# ProPrj_mfswControllerV1_2026-07-03.net
KiCad netlist of a schematic drawn in EasyEDA Pro
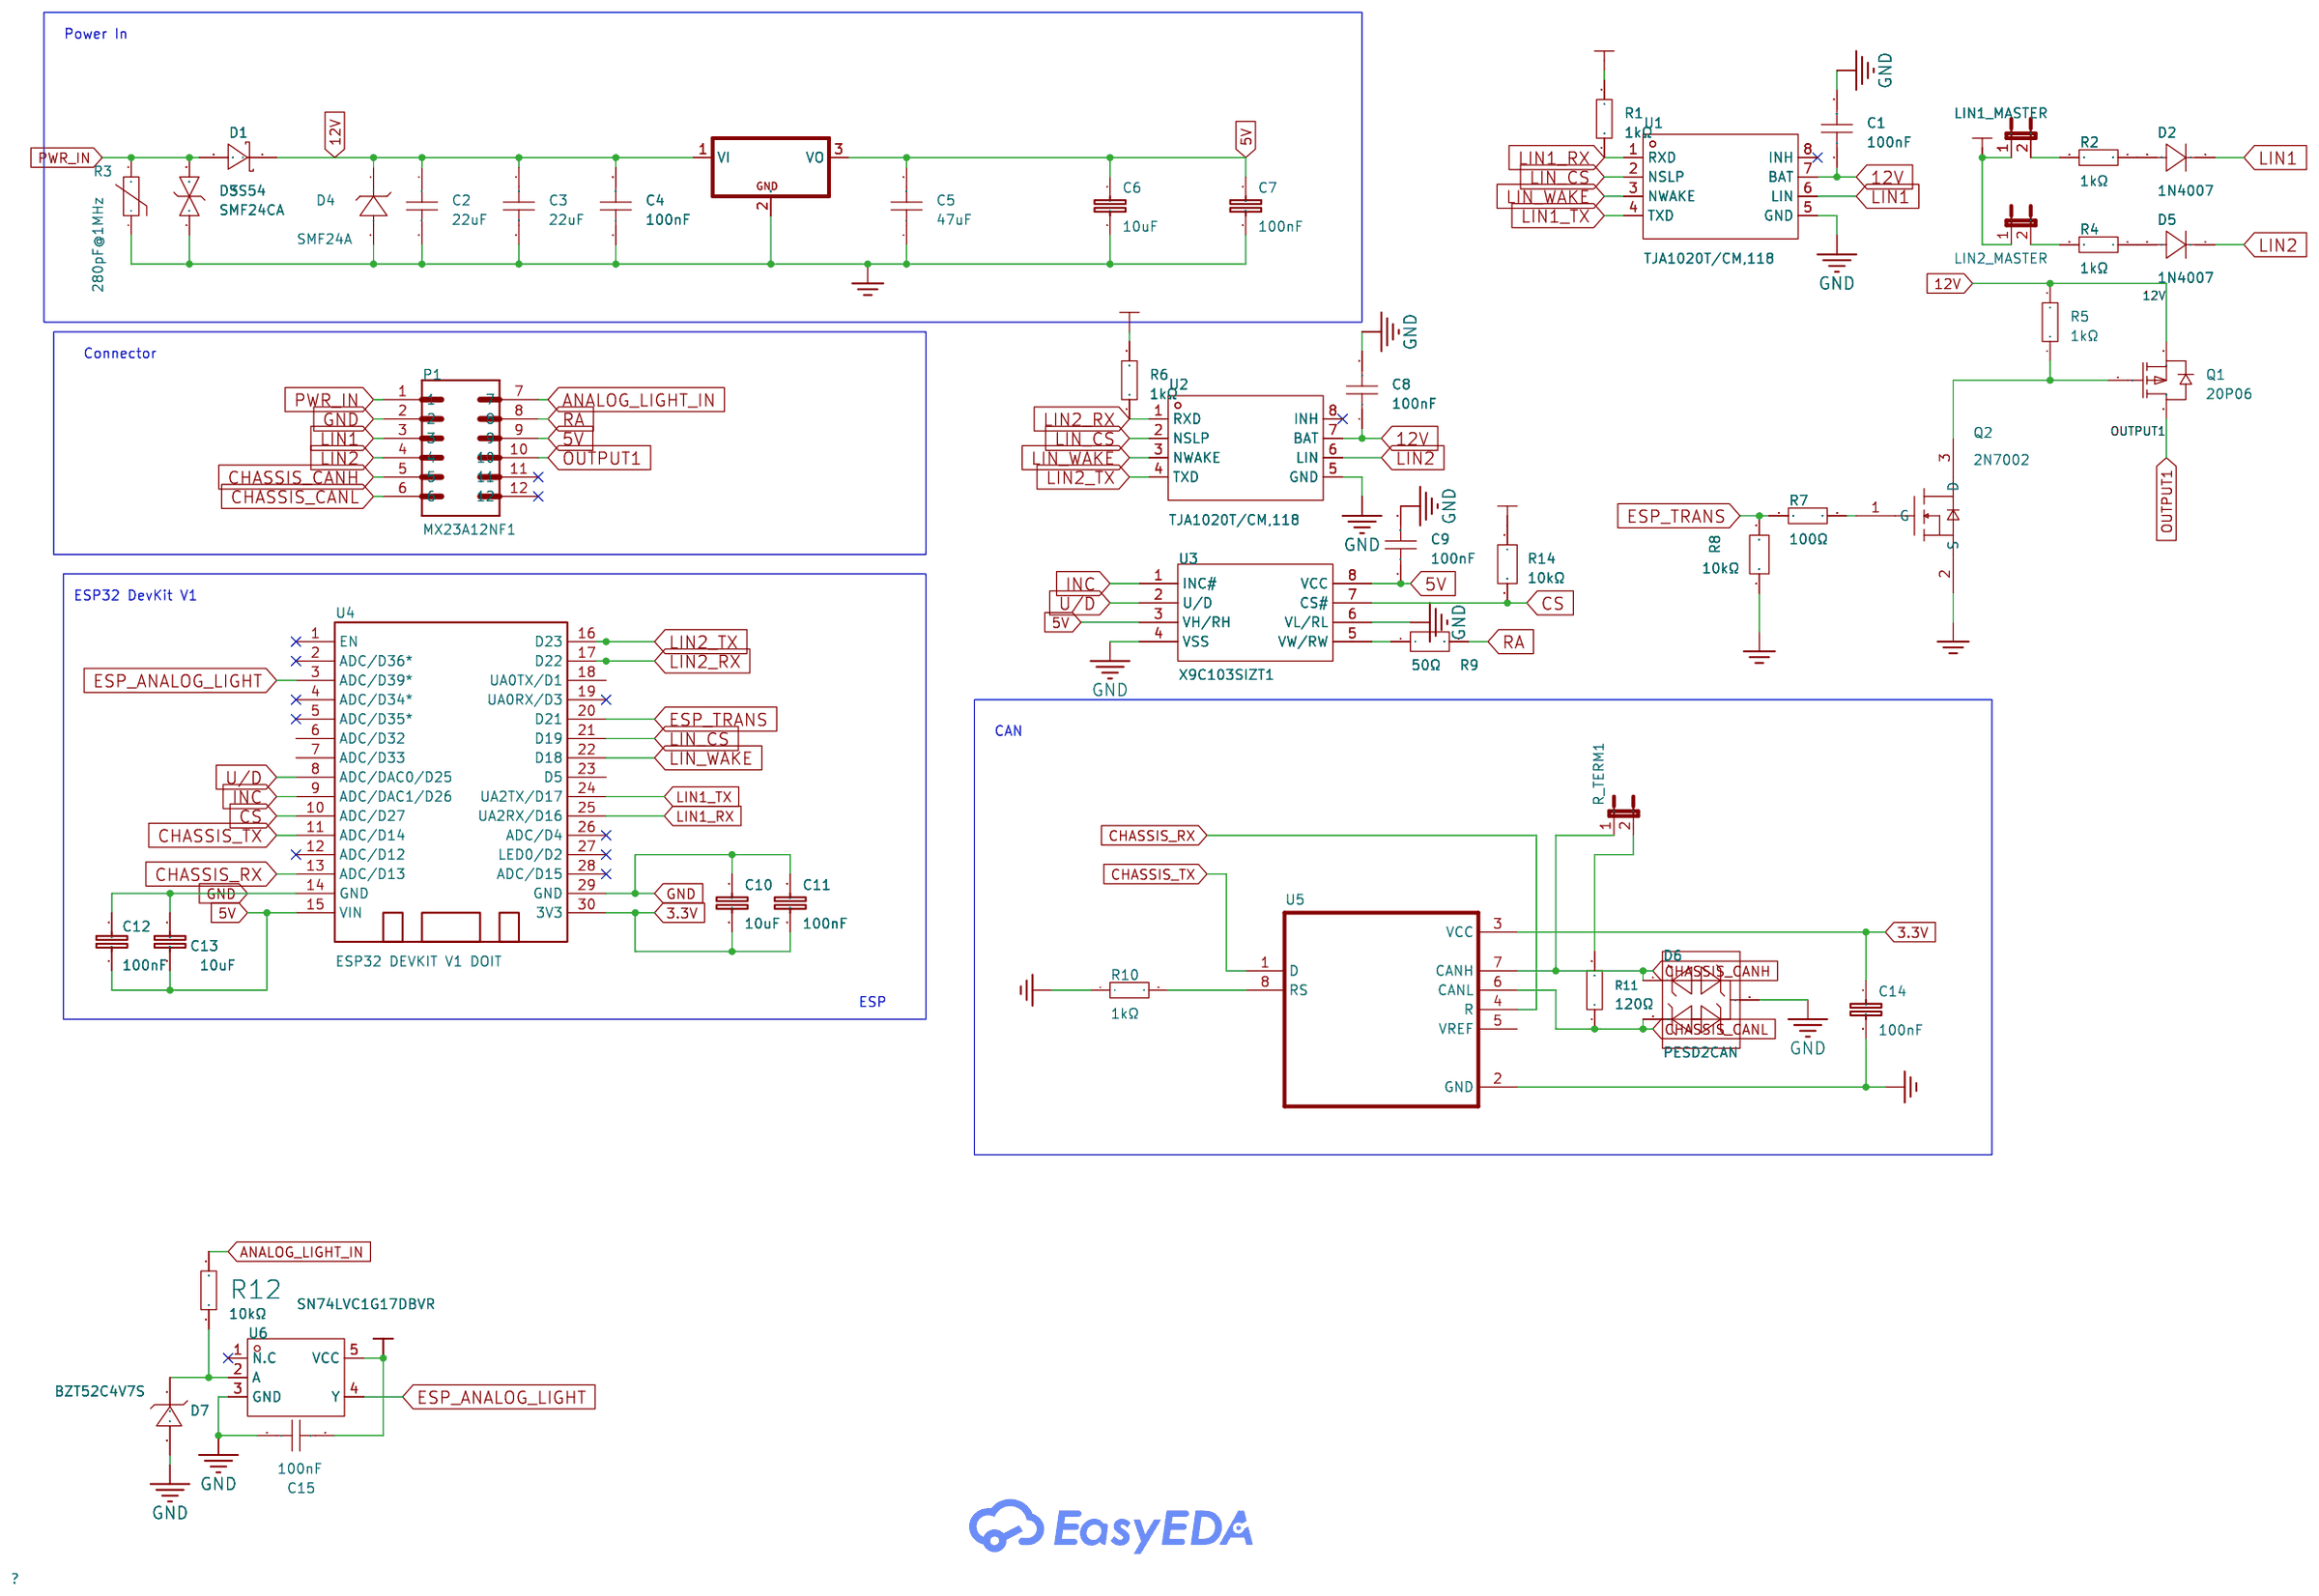
[diagram p0: schematic sheet]

(export (version "E")
  (design (tool "Eeschema 10.0.6"))
  (components
    (comp (ref "C1")
      (value "100nF")
      (footprint "easyedapro:C0603")
      (description "Capacitance:100nF Tolerance:±10% Tolerance:±10% Voltage Rating:50V Temperature Coefficient:X7R")
      (fields
        (field (name "Manufacturer Part") "CL10B104KB8NNNC")
        (field (name "Manufacturer") "SAMSUNG(三星)")
      )
      (libsource (lib "easyedapro") (part "CC0603KRX7R9BB104"))
    )
    (comp (ref "C2")
      (value "22uF")
      (footprint "easyedapro:C0805")
      (fields
        (field (name "Manufacturer Part") "HGC0805R5226M350NSLJ")
        (field (name "Manufacturer") "Chinocera(华瓷)")
      )
      (libsource (lib "easyedapro") (part "HGC0805R5226M350NSLJ"))
    )
    (comp (ref "C3")
      (value "22uF")
      (footprint "easyedapro:C0805")
      (fields
        (field (name "Manufacturer Part") "HGC0805R5226M350NSLJ")
        (field (name "Manufacturer") "Chinocera(华瓷)")
      )
      (libsource (lib "easyedapro") (part "HGC0805R5226M350NSLJ"))
    )
    (comp (ref "C4")
      (value "100nF")
      (description "Capacitance:100nF Tolerance:±10% Tolerance:±10% Voltage Rating:50V Temperature Coefficient:X7R")
      (fields
        (field (name "Manufacturer Part") "CL10B104KB8NNNC")
        (field (name "Manufacturer") "SAMSUNG(三星)")
      )
      (libsource (lib "easyedapro") (part "CSA0603X7R104K500JT"))
    )
    (comp (ref "C5")
      (value "47uF")
      (footprint "easyedapro:C0805")
      (description "Capacitance:47uF Tolerance:±20% Tolerance:±20% Voltage Rating:10V Temperature Coefficient:X5R")
      (fields
        (field (name "Manufacturer Part") "CL21A476MPYNNWE")
        (field (name "Manufacturer") "SAMSUNG(三星)")
      )
      (libsource (lib "easyedapro") (part "CL21A476MPYNNWE"))
    )
    (comp (ref "C6")
      (value "10uF")
      (fields
        (field (name "Manufacturer Part") "CL21A106KAYNNNE")
        (field (name "Manufacturer") "SAMSUNG(三星)")
      )
      (libsource (lib "easyedapro") (part "capacitor-wima_C_2.5/2"))
    )
    (comp (ref "C7")
      (value "100nF")
      (description "Capacitance:100nF Tolerance:±10% Tolerance:±10% Voltage Rating:50V Temperature Coefficient:-")
      (fields
        (field (name "Manufacturer Part") "CT41G-0805-2X1-50V-0.1μF-K(N)")
        (field (name "Manufacturer") "TORCH(火炬)")
      )
      (libsource (lib "easyedapro") (part "capacitor-wima_C_2.5/2"))
    )
    (comp (ref "C8")
      (value "100nF")
      (footprint "easyedapro:C0603")
      (description "Capacitance:100nF Tolerance:±10% Tolerance:±10% Voltage Rating:50V Temperature Coefficient:X7R")
      (fields
        (field (name "Manufacturer Part") "CL10B104KB8NNNC")
        (field (name "Manufacturer") "SAMSUNG(三星)")
      )
      (libsource (lib "easyedapro") (part "CC0603KRX7R9BB104"))
    )
    (comp (ref "C9")
      (value "100nF")
      (footprint "easyedapro:C0603")
      (description "Capacitance:100nF Tolerance:±10% Tolerance:±10% Voltage Rating:50V Temperature Coefficient:X7R")
      (fields
        (field (name "Manufacturer Part") "CL10B104KB8NNNC")
        (field (name "Manufacturer") "SAMSUNG(三星)")
      )
      (libsource (lib "easyedapro") (part "CC0603KRX7R9BB104"))
    )
    (comp (ref "C10")
      (value "10uF")
      (fields
        (field (name "Manufacturer Part") "CL21A106KAYNNNE")
        (field (name "Manufacturer") "SAMSUNG(三星)")
      )
      (libsource (lib "easyedapro") (part "capacitor-wima_C_2.5/2"))
    )
    (comp (ref "C11")
      (value "100nF")
      (description "Capacitance:100nF Tolerance:±10% Tolerance:±10% Voltage Rating:50V Temperature Coefficient:X7R")
      (fields
        (field (name "Manufacturer Part") "CC0603KRX7R9BB104")
        (field (name "Manufacturer") "YAGEO(国巨)")
      )
      (libsource (lib "easyedapro") (part "capacitor-wima_C_2.5/2"))
    )
    (comp (ref "C12")
      (value "100nF")
      (description "Capacitance:100nF Tolerance:±10% Tolerance:±10% Voltage Rating:50V Temperature Coefficient:X7R")
      (fields
        (field (name "Manufacturer Part") "CC0603KRX7R9BB104")
        (field (name "Manufacturer") "YAGEO(国巨)")
      )
      (libsource (lib "easyedapro") (part "capacitor-wima_C_2.5/2"))
    )
    (comp (ref "C13")
      (value "10uF")
      (fields
        (field (name "Manufacturer Part") "CL21A106KAYNNNE")
        (field (name "Manufacturer") "SAMSUNG(三星)")
      )
      (libsource (lib "easyedapro") (part "capacitor-wima_C_2.5/2"))
    )
    (comp (ref "C14")
      (value "100nF")
      (description "Capacitance:100nF Tolerance:±10% Tolerance:±10% Voltage Rating:50V Temperature Coefficient:-")
      (fields
        (field (name "Manufacturer Part") "CT41G-0805-2X1-50V-0.1μF-K(N)")
        (field (name "Manufacturer") "TORCH(火炬)")
      )
      (libsource (lib "easyedapro") (part "capacitor-wima_C_2.5/2"))
    )
    (comp (ref "C15")
      (value "100nF")
      (footprint "easyedapro:C0603")
      (description "Capacitance:100nF Tolerance:±10% Tolerance:±10% Voltage Rating:50V Temperature Coefficient:X7R")
      (fields
        (field (name "Manufacturer Part") "CL10B104KB8NNNC")
        (field (name "Manufacturer") "SAMSUNG(三星)")
      )
      (libsource (lib "easyedapro") (part "CC0603KRX7R9BB104"))
    )
    (comp (ref "D1")
      (value "SS54")
      (footprint "easyedapro:SMA_L4.4-W2.8-LS5.4-R-RD")
      (fields (field (name "Manufacturer") "MDD(辰达半导体)"))
      (libsource (lib "easyedapro") (part "SS54_C22452"))
    )
    (comp (ref "D2")
      (value "1N4007")
      (footprint "easyedapro:SMA_L4.3-W2.5-LS5.0-RD")
      (fields (field (name "Manufacturer") "TWGMC(迪嘉)"))
      (libsource (lib "easyedapro") (part "1N4007_C727081"))
    )
    (comp (ref "D3")
      (value "SMF24CA")
      (footprint "easyedapro:SOD-123FL_L2.8-W1.8-LS3.7-BI")
      (fields (field (name "Manufacturer") "晶导微电子"))
      (libsource (lib "easyedapro") (part "SMF24CA_C353294"))
    )
    (comp (ref "D4")
      (value "SMF24A")
      (footprint "easyedapro:SOD-123FL_L2.7-W1.8-LS3.8-RD")
      (fields (field (name "Manufacturer") "R+O(宏嘉诚)"))
      (libsource (lib "easyedapro") (part "SMF24A_C19077514"))
    )
    (comp (ref "D5")
      (value "1N4007")
      (footprint "easyedapro:SMA_L4.3-W2.5-LS5.0-RD")
      (fields (field (name "Manufacturer") "TWGMC(迪嘉)"))
      (libsource (lib "easyedapro") (part "1N4007_C727081"))
    )
    (comp (ref "D6")
      (value "PESD2CAN")
      (footprint "easyedapro:SOT-23-3_L2.9-W1.3-P1.90-LS2.4-BR")
      (fields (field (name "Manufacturer") "TECH PUBLIC(台舟)"))
      (libsource (lib "easyedapro") (part "PESD2CAN_C907830"))
    )
    (comp (ref "D7")
      (value "BZT52C4V7S")
      (footprint "easyedapro:SOD-323_L1.8-W1.3-LS2.5-RD")
      (fields (field (name "Manufacturer") "晶导微电子"))
      (libsource (lib "easyedapro") (part "BZT52C4V7S_C353517"))
    )
    (comp (ref "IC1")
      (value "L7805ABD2T-TR")
      (fields (field (name "Manufacturer") "ST(意法半导体)"))
      (libsource (lib "easyedapro") (part "linear_78*_TV"))
    )
    (comp (ref "LIN1_MASTER")
      (value "PZ254V-11-02P")
      (fields (field (name "Manufacturer") "XFCN(兴飞)"))
      (libsource (lib "easyedapro") (part "jumper_JP1E_"))
    )
    (comp (ref "LIN2_MASTER")
      (value "PZ254V-11-02P")
      (fields (field (name "Manufacturer") "XFCN(兴飞)"))
      (libsource (lib "easyedapro") (part "jumper_JP1E_"))
    )
    (comp (ref "P1")
      (value "MX23A12NF1")
      (fields (field (name "Manufacturer") "JAE(日本航空电子)"))
      (libsource (lib "easyedapro") (part "MX23A12NF1_MX23A12NF1_"))
    )
    (comp (ref "Q1")
      (value "20P06")
      (footprint "easyedapro:TO-252-2_L6.6-W6.1-P4.57-LS9.9-BR-CW")
      (fields (field (name "Manufacturer") "HL(富海微)"))
      (libsource (lib "easyedapro") (part "20P06"))
    )
    (comp (ref "Q2")
      (value "2N7002")
      (footprint "easyedapro:SOT-23-3_L2.9-W1.3-P1.90-LS2.4-BR")
      (fields (field (name "Manufacturer") "JSMSEMI(杰盛微)"))
      (libsource (lib "easyedapro") (part "2N7002_C916396"))
    )
    (comp (ref "R1")
      (value "1kΩ")
      (footprint "easyedapro:R0603")
      (fields
        (field (name "Manufacturer Part") "0603WAF1001T5E")
        (field (name "Manufacturer") "UNI-ROYAL(厚声)")
      )
      (libsource (lib "easyedapro") (part "0603WAF1001T5E"))
    )
    (comp (ref "R2")
      (value "1kΩ")
      (footprint "easyedapro:R0603")
      (fields
        (field (name "Manufacturer Part") "0603WAF1001T5E")
        (field (name "Manufacturer") "UNI-ROYAL(厚声)")
      )
      (libsource (lib "easyedapro") (part "0603WAF1001T5E"))
    )
    (comp (ref "R3")
      (value "280pF@1MHz")
      (footprint "easyedapro:R0805")
      (fields (field (name "Manufacturer Part") "FPV201209E260PKT") (field (name "Manufacturer") "FH(风华)"))
      (libsource (lib "easyedapro") (part "FPV201209E260PKT"))
    )
    (comp (ref "R4")
      (value "1kΩ")
      (footprint "easyedapro:R0603")
      (fields
        (field (name "Manufacturer Part") "0603WAF1001T5E")
        (field (name "Manufacturer") "UNI-ROYAL(厚声)")
      )
      (libsource (lib "easyedapro") (part "0603WAF1001T5E"))
    )
    (comp (ref "R5")
      (value "1kΩ")
      (fields
        (field (name "Manufacturer Part") "0603WAF1001T5E")
        (field (name "Manufacturer") "UNI-ROYAL(厚声)")
      )
      (libsource (lib "easyedapro") (part "0603WAF3300T5E"))
    )
    (comp (ref "R6")
      (value "1kΩ")
      (footprint "easyedapro:R0603")
      (fields
        (field (name "Manufacturer Part") "0603WAF1001T5E")
        (field (name "Manufacturer") "UNI-ROYAL(厚声)")
      )
      (libsource (lib "easyedapro") (part "0603WAF1001T5E"))
    )
    (comp (ref "R7")
      (value "100Ω")
      (footprint "easyedapro:R0603")
      (fields (field (name "Manufacturer Part") "RT0603BRD07100RL") (field (name "Manufacturer") "YAGEO(国巨)"))
      (libsource (lib "easyedapro") (part "RT0603BRD07100RL"))
    )
    (comp (ref "R8")
      (value "10kΩ")
      (footprint "easyedapro:R0603")
      (fields (field (name "Manufacturer Part") "ESR03EZPF1002") (field (name "Manufacturer") "ROHM(罗姆)"))
      (libsource (lib "easyedapro") (part "FRC0603J103TS"))
    )
    (comp (ref "R9")
      (value "50Ω")
      (footprint "easyedapro:R0402")
      (fields (field (name "Manufacturer Part") "FRC0402F50R0TS") (field (name "Manufacturer") "FOJAN(富捷)"))
      (libsource (lib "easyedapro") (part "FRC0402F50R0TS"))
    )
    (comp (ref "R10")
      (value "1kΩ")
      (footprint "easyedapro:R0603")
      (fields
        (field (name "Manufacturer Part") "0603WAF1001T5E")
        (field (name "Manufacturer") "UNI-ROYAL(厚声)")
      )
      (libsource (lib "easyedapro") (part "0603WAF1001T5E"))
    )
    (comp (ref "R11")
      (value "120Ω")
      (footprint "easyedapro:R0603")
      (fields
        (field (name "Manufacturer Part") "0603WAF1200T5E")
        (field (name "Manufacturer") "UNI-ROYAL(厚声)")
      )
      (libsource (lib "easyedapro") (part "0603WAF1200T5E"))
    )
    (comp (ref "R12")
      (value "10kΩ")
      (footprint "easyedapro:R0603")
      (fields (field (name "Manufacturer Part") "ESR03EZPF1002") (field (name "Manufacturer") "ROHM(罗姆)"))
      (libsource (lib "easyedapro") (part "0603WAF1002T5E"))
    )
    (comp (ref "R14")
      (value "10kΩ")
      (footprint "easyedapro:R0603")
      (fields (field (name "Manufacturer Part") "ESR03EZPF1002") (field (name "Manufacturer") "ROHM(罗姆)"))
      (libsource (lib "easyedapro") (part "FRC0603J103TS"))
    )
    (comp (ref "R_TERM1")
      (value "PZ254V-11-02P")
      (fields (field (name "Manufacturer") "XFCN(兴飞)"))
      (libsource (lib "easyedapro") (part "jumper_JP1E_"))
    )
    (comp (ref "U1")
      (value "TJA1020T/CM,118")
      (footprint "easyedapro:SOIC-8_L4.9-W3.9-P1.27-LS6.0-BL")
      (fields (field (name "Manufacturer") "NXP(恩智浦)"))
      (libsource (lib "easyedapro") (part "TJA1020T/CM,118"))
    )
    (comp (ref "U2")
      (value "TJA1020T/CM,118")
      (footprint "easyedapro:SOIC-8_L4.9-W3.9-P1.27-LS6.0-BL")
      (fields (field (name "Manufacturer") "NXP(恩智浦)"))
      (libsource (lib "easyedapro") (part "TJA1020T/CM,118"))
    )
    (comp (ref "U3")
      (value "X9C103SIZT1")
      (footprint "easyedapro:SOIC-8_L5.0-W4.0-P1.27-LS6.0-BL")
      (fields (field (name "Manufacturer") "RENESAS(瑞萨)/IDT"))
      (libsource (lib "easyedapro") (part "X9C103SIZT1"))
    )
    (comp (ref "U4")
      (value "ESP32 DEVKIT V1 DOIT")
      (footprint "easyedapro:DOIT-ESP32-DEVKIT-V1")
      (libsource (lib "easyedapro") (part "ESP32 DEVKIT V1 DOIT"))
    )
    (comp (ref "U5")
      (value "SN65HVD230DR")
      (fields (field (name "Manufacturer") "TI(德州仪器)"))
      (libsource (lib "easyedapro") (part "SN65HVD230DR_SN65HVD230DR_"))
    )
    (comp (ref "U6")
      (value "SN74LVC1G17DBVR")
      (footprint "easyedapro:SOT-23-5_L3.0-W1.5-P0.95-LS2.8-BL")
      (fields (field (name "Manufacturer") "TECH PUBLIC(台舟)"))
      (libsource (lib "easyedapro") (part "SN74LVC1G17DBVR_C19829662"))
    )
  )
  (nets
    (net (code "1") (name "3.3V") (class "Default")
      (node (ref "C10") (pin "2") (pinfunction "2_2") (pintype "unspecified"))
      (node (ref "C11") (pin "2") (pinfunction "2_2") (pintype "unspecified"))
      (node (ref "C14") (pin "1") (pinfunction "1_1") (pintype "unspecified"))
      (node (ref "C15") (pin "2") (pinfunction "2_2") (pintype "unspecified"))
      (node (ref "R1") (pin "2") (pinfunction "2_2") (pintype "input"))
      (node (ref "R14") (pin "1") (pinfunction "1_1") (pintype "unspecified"))
      (node (ref "R6") (pin "2") (pinfunction "2_2") (pintype "input"))
      (node (ref "U4") (pin "30") (pinfunction "3V3_30") (pintype "bidirectional"))
      (node (ref "U5") (pin "3") (pinfunction "VCC_3") (pintype "unspecified"))
      (node (ref "U6") (pin "5") (pinfunction "VCC_5") (pintype "unspecified"))
    )
    (net (code "2") (name "5V") (class "Default")
      (node (ref "C12") (pin "1") (pinfunction "1_1") (pintype "unspecified"))
      (node (ref "C13") (pin "1") (pinfunction "1_1") (pintype "unspecified"))
      (node (ref "C5") (pin "2") (pinfunction "2_2") (pintype "unspecified"))
      (node (ref "C6") (pin "1") (pinfunction "1_1") (pintype "unspecified"))
      (node (ref "C7") (pin "1") (pinfunction "1_1") (pintype "unspecified"))
      (node (ref "C9") (pin "1") (pinfunction "1_1") (pintype "unspecified"))
      (node (ref "IC1") (pin "3") (pinfunction "VO_3") (pintype "unspecified"))
      (node (ref "P1") (pin "9") (pinfunction "9_9") (pintype "unspecified"))
      (node (ref "U3") (pin "3") (pinfunction "VH/RH_3") (pintype "unspecified"))
      (node (ref "U3") (pin "8") (pinfunction "VCC_8") (pintype "unspecified"))
      (node (ref "U4") (pin "15") (pinfunction "VIN_15") (pintype "input"))
    )
    (net (code "3") (name "12V") (class "Default")
      (node (ref "C1") (pin "1") (pinfunction "1_1") (pintype "unspecified"))
      (node (ref "C2") (pin "1") (pinfunction "1_1") (pintype "unspecified"))
      (node (ref "C3") (pin "1") (pinfunction "1_1") (pintype "unspecified"))
      (node (ref "C4") (pin "2") (pinfunction "2_2") (pintype "unspecified"))
      (node (ref "C8") (pin "1") (pinfunction "1_1") (pintype "unspecified"))
      (node (ref "D1") (pin "2") (pinfunction "K_2") (pintype "unspecified"))
      (node (ref "D4") (pin "1") (pinfunction "K_1") (pintype "unspecified"))
      (node (ref "IC1") (pin "1") (pinfunction "VI_1") (pintype "input"))
      (node (ref "LIN1_MASTER") (pin "1") (pinfunction "1_1") (pintype "unspecified"))
      (node (ref "LIN2_MASTER") (pin "1") (pinfunction "1_1") (pintype "unspecified"))
      (node (ref "Q1") (pin "3") (pinfunction "S_3") (pintype "unspecified"))
      (node (ref "R5") (pin "2") (pinfunction "2_2") (pintype "input"))
      (node (ref "U1") (pin "7") (pinfunction "BAT_7") (pintype "input"))
      (node (ref "U2") (pin "7") (pinfunction "BAT_7") (pintype "input"))
    )
    (net (code "4") (name "ANALOG_LIGHT_IN") (class "Default")
      (node (ref "P1") (pin "7") (pinfunction "7_7") (pintype "unspecified"))
      (node (ref "R12") (pin "2") (pinfunction "2_2") (pintype "input"))
    )
    (net (code "5") (name "CHASSIS_CANH") (class "Default")
      (node (ref "D6") (pin "1") (pinfunction "1_1") (pintype "unspecified"))
      (node (ref "P1") (pin "5") (pinfunction "5_5") (pintype "unspecified"))
      (node (ref "R_TERM1") (pin "1") (pinfunction "1_1") (pintype "unspecified"))
      (node (ref "U5") (pin "7") (pinfunction "CANH_7") (pintype "output"))
    )
    (net (code "6") (name "CHASSIS_CANL") (class "Default")
      (node (ref "D6") (pin "2") (pinfunction "2_2") (pintype "unspecified"))
      (node (ref "P1") (pin "6") (pinfunction "6_6") (pintype "unspecified"))
      (node (ref "R11") (pin "1") (pinfunction "1_1") (pintype "input"))
      (node (ref "U5") (pin "6") (pinfunction "CANL_6") (pintype "output"))
    )
    (net (code "7") (name "CHASSIS_RX") (class "Default")
      (node (ref "U4") (pin "13") (pinfunction "ADC/D13_13") (pintype "bidirectional"))
      (node (ref "U5") (pin "4") (pinfunction "R_4") (pintype "output"))
    )
    (net (code "8") (name "CHASSIS_TX") (class "Default")
      (node (ref "U4") (pin "11") (pinfunction "ADC/D14_11") (pintype "bidirectional"))
      (node (ref "U5") (pin "1") (pinfunction "D_1") (pintype "input"))
    )
    (net (code "9") (name "CS") (class "Default")
      (node (ref "R14") (pin "2") (pinfunction "2_2") (pintype "unspecified"))
      (node (ref "U3") (pin "7") (pinfunction "CS#_7") (pintype "unspecified"))
      (node (ref "U4") (pin "10") (pinfunction "ADC/D27_10") (pintype "bidirectional"))
    )
    (net (code "10") (name "ESP_ANALOG_LIGHT") (class "Default")
      (node (ref "U4") (pin "3") (pinfunction "ADC/D39*_3") (pintype "input"))
      (node (ref "U6") (pin "4") (pinfunction "Y_4") (pintype "unspecified"))
    )
    (net (code "11") (name "ESP_TRANS") (class "Default")
      (node (ref "R7") (pin "1") (pinfunction "1_1") (pintype "input"))
      (node (ref "R8") (pin "2") (pinfunction "2_2") (pintype "unspecified"))
      (node (ref "U4") (pin "20") (pinfunction "D21_20") (pintype "bidirectional"))
    )
    (net (code "12") (name "GND") (class "Default")
      (node (ref "C1") (pin "2") (pinfunction "2_2") (pintype "unspecified"))
      (node (ref "C10") (pin "1") (pinfunction "1_1") (pintype "unspecified"))
      (node (ref "C11") (pin "1") (pinfunction "1_1") (pintype "unspecified"))
      (node (ref "C12") (pin "2") (pinfunction "2_2") (pintype "unspecified"))
      (node (ref "C13") (pin "2") (pinfunction "2_2") (pintype "unspecified"))
      (node (ref "C14") (pin "2") (pinfunction "2_2") (pintype "unspecified"))
      (node (ref "C15") (pin "1") (pinfunction "1_1") (pintype "unspecified"))
      (node (ref "C2") (pin "2") (pinfunction "2_2") (pintype "unspecified"))
      (node (ref "C3") (pin "2") (pinfunction "2_2") (pintype "unspecified"))
      (node (ref "C4") (pin "1") (pinfunction "1_1") (pintype "unspecified"))
      (node (ref "C5") (pin "1") (pinfunction "1_1") (pintype "unspecified"))
      (node (ref "C6") (pin "2") (pinfunction "2_2") (pintype "unspecified"))
      (node (ref "C7") (pin "2") (pinfunction "2_2") (pintype "unspecified"))
      (node (ref "C8") (pin "2") (pinfunction "2_2") (pintype "unspecified"))
      (node (ref "C9") (pin "2") (pinfunction "2_2") (pintype "unspecified"))
      (node (ref "D3") (pin "1") (pinfunction "1_1") (pintype "input"))
      (node (ref "D4") (pin "2") (pinfunction "A_2") (pintype "unspecified"))
      (node (ref "D6") (pin "3") (pinfunction "3_3") (pintype "unspecified"))
      (node (ref "D7") (pin "2") (pinfunction "A_2") (pintype "unspecified"))
      (node (ref "IC1") (pin "2") (pinfunction "GND_2") (pintype "unspecified"))
      (node (ref "P1") (pin "2") (pinfunction "2_2") (pintype "unspecified"))
      (node (ref "Q2") (pin "2") (pinfunction "S_2") (pintype "unspecified"))
      (node (ref "R10") (pin "1") (pinfunction "1_1") (pintype "input"))
      (node (ref "R3") (pin "1") (pinfunction "1_1") (pintype "unspecified"))
      (node (ref "R8") (pin "1") (pinfunction "1_1") (pintype "unspecified"))
      (node (ref "U1") (pin "5") (pinfunction "GND_5") (pintype "input"))
      (node (ref "U2") (pin "5") (pinfunction "GND_5") (pintype "input"))
      (node (ref "U3") (pin "4") (pinfunction "VSS_4") (pintype "unspecified"))
      (node (ref "U3") (pin "6") (pinfunction "VL/RL_6") (pintype "unspecified"))
      (node (ref "U4") (pin "14") (pinfunction "GND_14") (pintype "bidirectional"))
      (node (ref "U4") (pin "29") (pinfunction "GND_29") (pintype "bidirectional"))
      (node (ref "U5") (pin "2") (pinfunction "GND_2") (pintype "unspecified"))
      (node (ref "U6") (pin "3") (pinfunction "GND_3") (pintype "unspecified"))
    )
    (net (code "13") (name "INC") (class "Default")
      (node (ref "U3") (pin "1") (pinfunction "INC#_1") (pintype "unspecified"))
      (node (ref "U4") (pin "9") (pinfunction "ADC/DAC1/D26_9") (pintype "bidirectional"))
    )
    (net (code "14") (name "LIN1") (class "Default")
      (node (ref "D2") (pin "1") (pinfunction "K_1") (pintype "unspecified"))
      (node (ref "P1") (pin "3") (pinfunction "3_3") (pintype "unspecified"))
      (node (ref "U1") (pin "6") (pinfunction "LIN_6") (pintype "input"))
    )
    (net (code "15") (name "LIN1_RX") (class "Default")
      (node (ref "R1") (pin "1") (pinfunction "1_1") (pintype "input"))
      (node (ref "U1") (pin "1") (pinfunction "RXD_1") (pintype "input"))
      (node (ref "U4") (pin "25") (pinfunction "UA2RX/D16_25") (pintype "bidirectional"))
    )
    (net (code "16") (name "LIN1_TX") (class "Default")
      (node (ref "U1") (pin "4") (pinfunction "TXD_4") (pintype "input"))
      (node (ref "U4") (pin "24") (pinfunction "UA2TX/D17_24") (pintype "bidirectional"))
    )
    (net (code "17") (name "LIN2") (class "Default")
      (node (ref "D5") (pin "1") (pinfunction "K_1") (pintype "unspecified"))
      (node (ref "P1") (pin "4") (pinfunction "4_4") (pintype "unspecified"))
      (node (ref "U2") (pin "6") (pinfunction "LIN_6") (pintype "input"))
    )
    (net (code "18") (name "LIN2_RX") (class "Default")
      (node (ref "R6") (pin "1") (pinfunction "1_1") (pintype "input"))
      (node (ref "U2") (pin "1") (pinfunction "RXD_1") (pintype "input"))
      (node (ref "U4") (pin "17") (pinfunction "D22_17") (pintype "bidirectional"))
    )
    (net (code "19") (name "LIN2_TX") (class "Default")
      (node (ref "U2") (pin "4") (pinfunction "TXD_4") (pintype "input"))
      (node (ref "U4") (pin "16") (pinfunction "D23_16") (pintype "bidirectional"))
    )
    (net (code "20") (name "LIN_CS") (class "Default")
      (node (ref "U1") (pin "2") (pinfunction "NSLP_2") (pintype "input"))
      (node (ref "U2") (pin "2") (pinfunction "NSLP_2") (pintype "input"))
      (node (ref "U4") (pin "21") (pinfunction "D19_21") (pintype "bidirectional"))
    )
    (net (code "21") (name "LIN_WAKE") (class "Default")
      (node (ref "U1") (pin "3") (pinfunction "NWAKE_3") (pintype "input"))
      (node (ref "U2") (pin "3") (pinfunction "NWAKE_3") (pintype "input"))
      (node (ref "U4") (pin "22") (pinfunction "D18_22") (pintype "bidirectional"))
    )
    (net (code "22") (name "Net-(D2-A)") (class "Default")
      (node (ref "D2") (pin "2") (pinfunction "A_2") (pintype "unspecified"))
      (node (ref "R2") (pin "1") (pinfunction "1_1") (pintype "input"))
    )
    (net (code "23") (name "Net-(D5-A)") (class "Default")
      (node (ref "D5") (pin "2") (pinfunction "A_2") (pintype "unspecified"))
      (node (ref "R4") (pin "1") (pinfunction "1_1") (pintype "input"))
    )
    (net (code "24") (name "Net-(D7-K)") (class "Default")
      (node (ref "D7") (pin "1") (pinfunction "K_1") (pintype "unspecified"))
      (node (ref "R12") (pin "1") (pinfunction "1_1") (pintype "input"))
      (node (ref "U6") (pin "2") (pinfunction "A_2") (pintype "unspecified"))
    )
    (net (code "25") (name "Net-(LIN1_MASTER-Pad2)") (class "Default")
      (node (ref "LIN1_MASTER") (pin "2") (pinfunction "2_2") (pintype "unspecified"))
      (node (ref "R2") (pin "2") (pinfunction "2_2") (pintype "input"))
    )
    (net (code "26") (name "Net-(LIN2_MASTER-Pad2)") (class "Default")
      (node (ref "LIN2_MASTER") (pin "2") (pinfunction "2_2") (pintype "unspecified"))
      (node (ref "R4") (pin "2") (pinfunction "2_2") (pintype "input"))
    )
    (net (code "27") (name "Net-(Q1-G)") (class "Default")
      (node (ref "Q1") (pin "1") (pinfunction "G_1") (pintype "unspecified"))
      (node (ref "Q2") (pin "3") (pinfunction "D_3") (pintype "unspecified"))
      (node (ref "R5") (pin "1") (pinfunction "1_1") (pintype "input"))
    )
    (net (code "28") (name "Net-(Q2-G)") (class "Default")
      (node (ref "Q2") (pin "1") (pinfunction "G_1") (pintype "unspecified"))
      (node (ref "R7") (pin "2") (pinfunction "2_2") (pintype "input"))
    )
    (net (code "29") (name "Net-(R11-Pad2)") (class "Default")
      (node (ref "R11") (pin "2") (pinfunction "2_2") (pintype "input"))
      (node (ref "R_TERM1") (pin "2") (pinfunction "2_2") (pintype "unspecified"))
    )
    (net (code "30") (name "Net-(U3-VW{slash}RW)") (class "Default")
      (node (ref "R9") (pin "1") (pinfunction "1_1") (pintype "unspecified"))
      (node (ref "U3") (pin "5") (pinfunction "VW/RW_5") (pintype "unspecified"))
    )
    (net (code "31") (name "Net-(U5-RS)") (class "Default")
      (node (ref "R10") (pin "2") (pinfunction "2_2") (pintype "input"))
      (node (ref "U5") (pin "8") (pinfunction "RS_8") (pintype "input"))
    )
    (net (code "32") (name "OUTPUT1") (class "Default")
      (node (ref "P1") (pin "10") (pinfunction "10_10") (pintype "unspecified"))
      (node (ref "Q1") (pin "2") (pinfunction "D_2") (pintype "unspecified"))
    )
    (net (code "33") (name "PWR_IN") (class "Default")
      (node (ref "D1") (pin "1") (pinfunction "A_1") (pintype "unspecified"))
      (node (ref "D3") (pin "2") (pinfunction "2_2") (pintype "input"))
      (node (ref "P1") (pin "1") (pinfunction "1_1") (pintype "unspecified"))
      (node (ref "R3") (pin "2") (pinfunction "2_2") (pintype "unspecified"))
    )
    (net (code "34") (name "RA") (class "Default")
      (node (ref "P1") (pin "8") (pinfunction "8_8") (pintype "unspecified"))
      (node (ref "R9") (pin "2") (pinfunction "2_2") (pintype "unspecified"))
    )
    (net (code "35") (name "U{slash}D") (class "Default")
      (node (ref "U3") (pin "2") (pinfunction "U/D_2") (pintype "unspecified"))
      (node (ref "U4") (pin "8") (pinfunction "ADC/DAC0/D25_8") (pintype "bidirectional"))
    )
    (net (code "36") (name "unconnected-(P1-Pad11)") (class "Default")
      (node (ref "P1") (pin "11") (pinfunction "11_11") (pintype "unspecified+no_connect"))
    )
    (net (code "37") (name "unconnected-(P1-Pad12)") (class "Default")
      (node (ref "P1") (pin "12") (pinfunction "12_12") (pintype "unspecified+no_connect"))
    )
    (net (code "38") (name "unconnected-(U1-INH-Pad8)") (class "Default")
      (node (ref "U1") (pin "8") (pinfunction "INH_8") (pintype "input+no_connect"))
    )
    (net (code "39") (name "unconnected-(U2-INH-Pad8)") (class "Default")
      (node (ref "U2") (pin "8") (pinfunction "INH_8") (pintype "input+no_connect"))
    )
    (net (code "40") (name "unconnected-(U4-ADC{slash}D4-Pad26)") (class "Default")
      (node (ref "U4") (pin "26") (pinfunction "ADC/D4_26") (pintype "bidirectional+no_connect"))
    )
    (net (code "41") (name "unconnected-(U4-ADC{slash}D12-Pad12)") (class "Default")
      (node (ref "U4") (pin "12") (pinfunction "ADC/D12_12") (pintype "bidirectional+no_connect"))
    )
    (net (code "42") (name "unconnected-(U4-ADC{slash}D15-Pad28)") (class "Default")
      (node (ref "U4") (pin "28") (pinfunction "ADC/D15_28") (pintype "bidirectional+no_connect"))
    )
    (net (code "43") (name "unconnected-(U4-ADC{slash}D32-Pad6)") (class "Default")
      (node (ref "U4") (pin "6") (pinfunction "ADC/D32_6") (pintype "bidirectional"))
    )
    (net (code "44") (name "unconnected-(U4-ADC{slash}D33-Pad7)") (class "Default")
      (node (ref "U4") (pin "7") (pinfunction "ADC/D33_7") (pintype "bidirectional"))
    )
    (net (code "45") (name "unconnected-(U4-ADC{slash}D34*-Pad4)") (class "Default")
      (node (ref "U4") (pin "4") (pinfunction "ADC/D34*_4") (pintype "input+no_connect"))
    )
    (net (code "46") (name "unconnected-(U4-ADC{slash}D35*-Pad5)") (class "Default")
      (node (ref "U4") (pin "5") (pinfunction "ADC/D35*_5") (pintype "input+no_connect"))
    )
    (net (code "47") (name "unconnected-(U4-ADC{slash}D36*-Pad2)") (class "Default")
      (node (ref "U4") (pin "2") (pinfunction "ADC/D36*_2") (pintype "input+no_connect"))
    )
    (net (code "48") (name "unconnected-(U4-D5-Pad23)") (class "Default")
      (node (ref "U4") (pin "23") (pinfunction "D5_23") (pintype "bidirectional"))
    )
    (net (code "49") (name "unconnected-(U4-EN-Pad1)") (class "Default")
      (node (ref "U4") (pin "1") (pinfunction "EN_1") (pintype "bidirectional+no_connect"))
    )
    (net (code "50") (name "unconnected-(U4-LED0{slash}D2-Pad27)") (class "Default")
      (node (ref "U4") (pin "27") (pinfunction "LED0/D2_27") (pintype "bidirectional+no_connect"))
    )
    (net (code "51") (name "unconnected-(U4-UA0RX{slash}D3-Pad19)") (class "Default")
      (node (ref "U4") (pin "19") (pinfunction "UA0RX/D3_19") (pintype "bidirectional+no_connect"))
    )
    (net (code "52") (name "unconnected-(U4-UA0TX{slash}D1-Pad18)") (class "Default")
      (node (ref "U4") (pin "18") (pinfunction "UA0TX/D1_18") (pintype "bidirectional"))
    )
    (net (code "53") (name "unconnected-(U5-VREF-Pad5)") (class "Default")
      (node (ref "U5") (pin "5") (pinfunction "VREF_5") (pintype "output"))
    )
    (net (code "54") (name "unconnected-(U6-N.C-Pad1)") (class "Default")
      (node (ref "U6") (pin "1") (pinfunction "N.C_1") (pintype "unspecified+no_connect"))
    )
  )
)
